# Radial-V_Alim.net
KiCad netlist of a schematic drawn in EAGLE
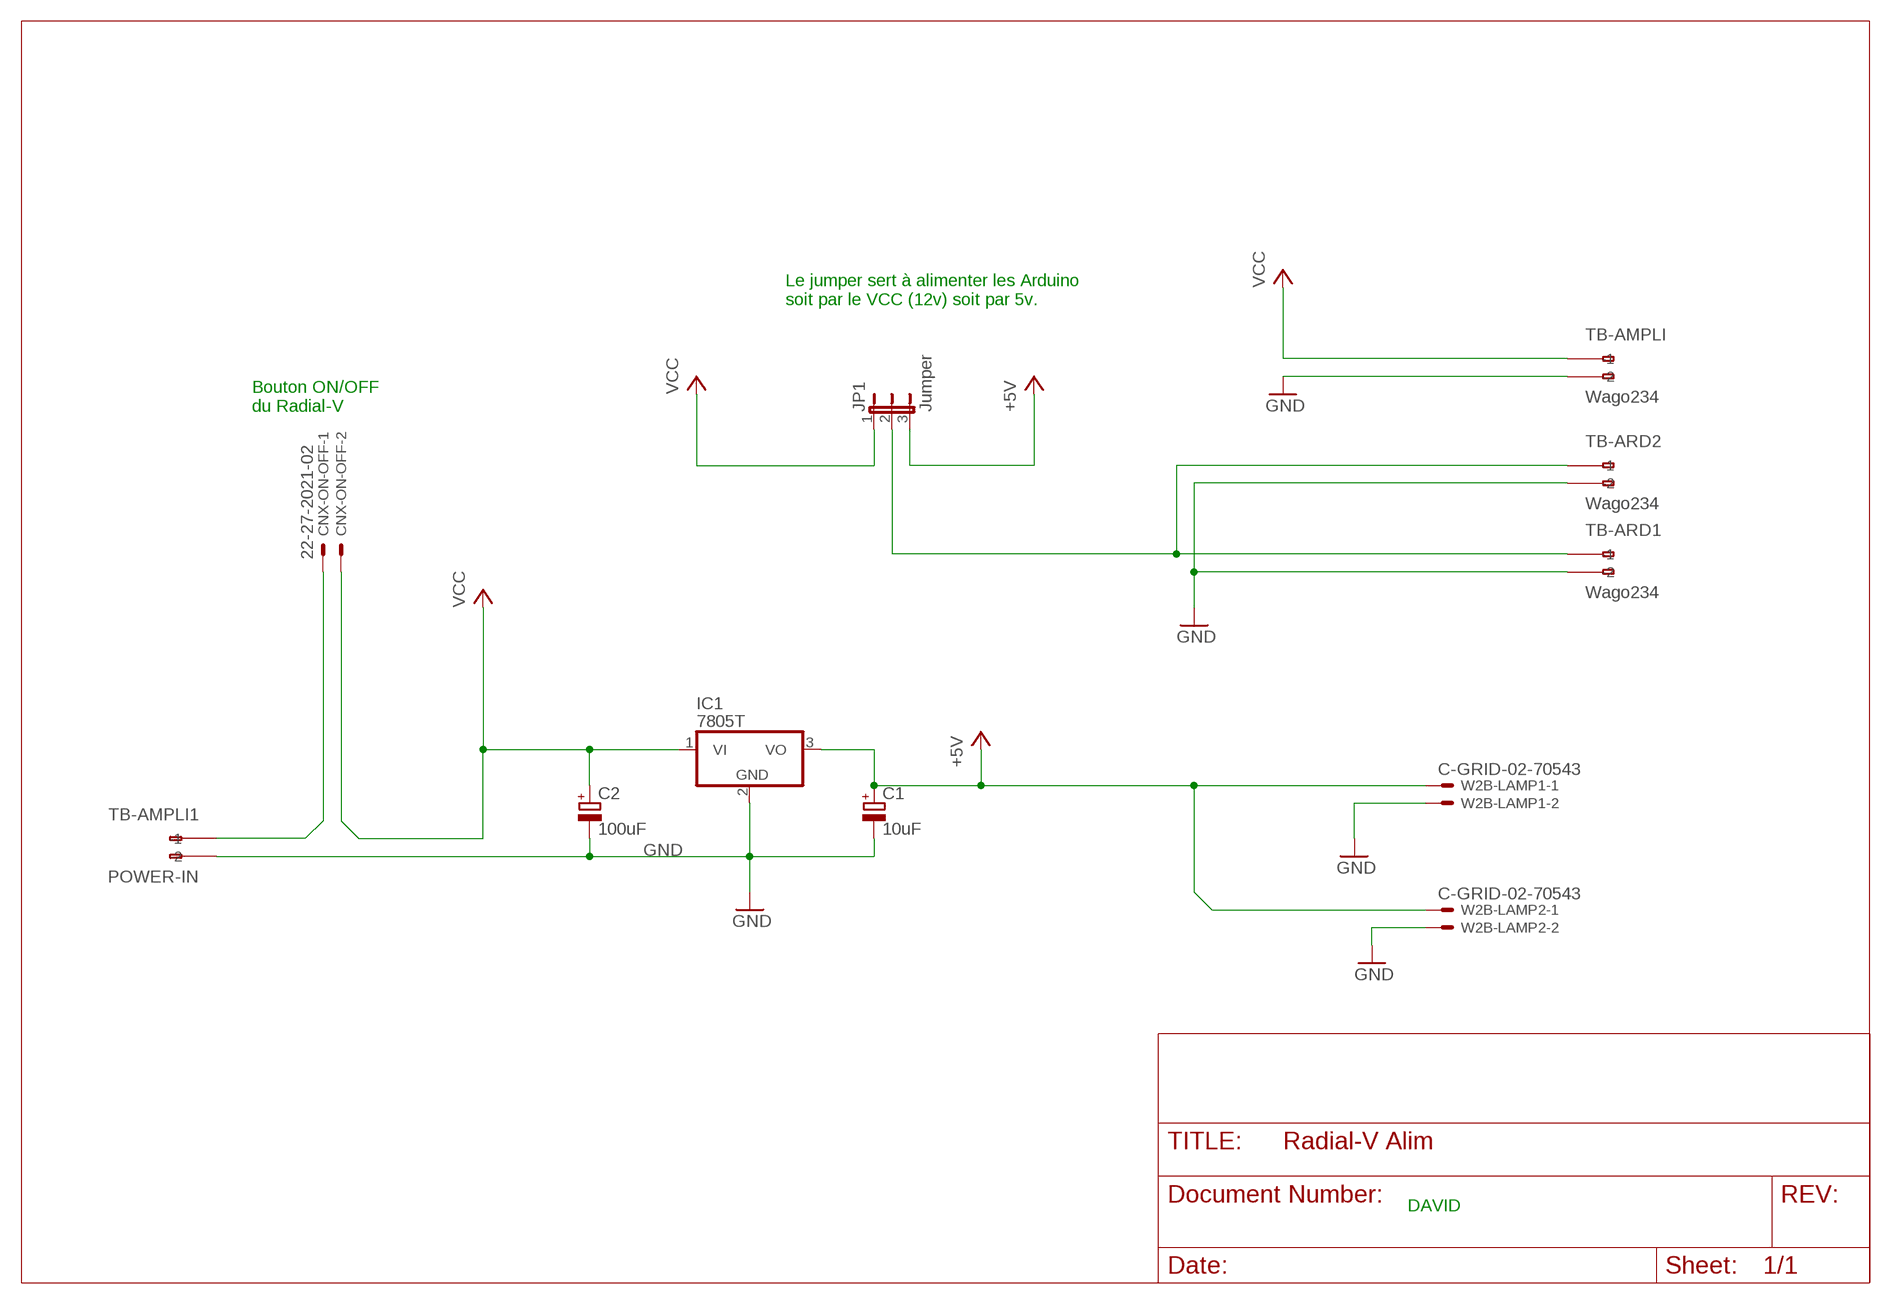
[diagram p0: schematic, sheet 1]

(export (version "E")
  (design (tool "Eeschema 10.0.6"))
  (components
    (comp (ref "C1")
      (value "10uF")
      (footprint "eagle-import:E5-5")
      (libsource (lib "eagle-import") (part "CPOL-EUE5-5"))
    )
    (comp (ref "C2")
      (value "100uF")
      (footprint "eagle-import:E22-10")
      (libsource (lib "eagle-import") (part "CPOL-EUE22-10AXIAL"))
    )
    (comp (ref "CNX-ON-OFF")
      (value "22-27-2021-02")
      (footprint "eagle-import:6410-02")
      (libsource (lib "eagle-import") (part "22-?-0227-2021"))
    )
    (comp (ref "IC1")
      (value "7805T")
      (footprint "eagle-import:TO220H")
      (libsource (lib "eagle-import") (part "78T05"))
    )
    (comp (ref "JP1")
      (value "Jumper")
      (footprint "eagle-import:JP2")
      (libsource (lib "eagle-import") (part "JP2E"))
    )
    (comp (ref "TB-AMPLI")
      (value "Wago234")
      (footprint "eagle-import:234-202")
      (fields (field (name "MPN") "234-202"))
      (libsource (lib "eagle-import") (part "234-202"))
    )
    (comp (ref "TB-AMPLI1")
      (value "POWER-IN")
      (footprint "eagle-import:234-202")
      (fields (field (name "MPN") "234-202"))
      (libsource (lib "eagle-import") (part "234-202"))
    )
    (comp (ref "TB-ARD1")
      (value "Wago234")
      (footprint "eagle-import:234-202")
      (fields (field (name "MPN") "234-202"))
      (libsource (lib "eagle-import") (part "234-202"))
    )
    (comp (ref "TB-ARD2")
      (value "Wago234")
      (footprint "eagle-import:234-202")
      (fields (field (name "MPN") "234-202"))
      (libsource (lib "eagle-import") (part "234-202"))
    )
    (comp (ref "W2B-LAMP1")
      (value "C-GRID-02-70543")
      (footprint "eagle-import:70543-02")
      (libsource (lib "eagle-import") (part "C-GRID-02-70543"))
    )
    (comp (ref "W2B-LAMP2")
      (value "C-GRID-02-70543")
      (footprint "eagle-import:70543-02")
      (libsource (lib "eagle-import") (part "C-GRID-02-70543"))
    )
  )
  (nets
    (net (code "1") (name "+5V") (class "Default")
      (node (ref "C1") (pin "+") (pinfunction "+_+") (pintype "passive"))
      (node (ref "IC1") (pin "3") (pinfunction "VO_3") (pintype "passive"))
      (node (ref "JP1") (pin "3") (pinfunction "3_3") (pintype "passive"))
      (node (ref "W2B-LAMP1") (pin "1") (pinfunction "S_1") (pintype "passive"))
      (node (ref "W2B-LAMP2") (pin "1") (pinfunction "S_1") (pintype "passive"))
    )
    (net (code "2") (name "GND") (class "Default")
      (node (ref "C1") (pin "-") (pinfunction "-_-") (pintype "passive"))
      (node (ref "C2") (pin "-") (pinfunction "-_-") (pintype "passive"))
      (node (ref "IC1") (pin "2") (pinfunction "GND_2") (pintype "passive"))
      (node (ref "TB-AMPLI") (pin "A2") (pinfunction "-2_A2") (pintype "passive"))
      (node (ref "TB-AMPLI1") (pin "A2") (pinfunction "-2_A2") (pintype "passive"))
      (node (ref "TB-ARD1") (pin "A2") (pinfunction "-2_A2") (pintype "passive"))
      (node (ref "TB-ARD2") (pin "A2") (pinfunction "-2_A2") (pintype "passive"))
      (node (ref "W2B-LAMP1") (pin "2") (pinfunction "S_2") (pintype "passive"))
      (node (ref "W2B-LAMP2") (pin "2") (pinfunction "S_2") (pintype "passive"))
    )
    (net (code "3") (name "Net-(CNX-ON-OFFA-S)") (class "Default")
      (node (ref "CNX-ON-OFF") (pin "1") (pinfunction "S_1") (pintype "passive"))
      (node (ref "TB-AMPLI1") (pin "A1") (pinfunction "-1_A1") (pintype "passive"))
    )
    (net (code "4") (name "Net-(TB-ARD1--1)") (class "Default")
      (node (ref "JP1") (pin "2") (pinfunction "2_2") (pintype "passive"))
      (node (ref "TB-ARD1") (pin "A1") (pinfunction "-1_A1") (pintype "passive"))
      (node (ref "TB-ARD2") (pin "A1") (pinfunction "-1_A1") (pintype "passive"))
    )
    (net (code "5") (name "VCC") (class "Default")
      (node (ref "C2") (pin "+") (pinfunction "+_+") (pintype "passive"))
      (node (ref "CNX-ON-OFF") (pin "2") (pinfunction "S_2") (pintype "passive"))
      (node (ref "IC1") (pin "1") (pinfunction "VI_1") (pintype "input"))
      (node (ref "JP1") (pin "1") (pinfunction "1_1") (pintype "passive"))
      (node (ref "TB-AMPLI") (pin "A1") (pinfunction "-1_A1") (pintype "passive"))
    )
    (net (code "6") (name "unconnected-(TB-AMPLI-B-1-PadB1)") (class "Default")
      (node (ref "TB-AMPLI") (pin "B1") (pinfunction "B-1_B1") (pintype "passive"))
    )
    (net (code "7") (name "unconnected-(TB-AMPLI-B-2-PadB2)") (class "Default")
      (node (ref "TB-AMPLI") (pin "B2") (pinfunction "B-2_B2") (pintype "passive"))
    )
    (net (code "8") (name "unconnected-(TB-AMPLI1-B-1-PadB1)") (class "Default")
      (node (ref "TB-AMPLI1") (pin "B1") (pinfunction "B-1_B1") (pintype "passive"))
    )
    (net (code "9") (name "unconnected-(TB-AMPLI1-B-2-PadB2)") (class "Default")
      (node (ref "TB-AMPLI1") (pin "B2") (pinfunction "B-2_B2") (pintype "passive"))
    )
    (net (code "10") (name "unconnected-(TB-ARD1-B-1-PadB1)") (class "Default")
      (node (ref "TB-ARD1") (pin "B1") (pinfunction "B-1_B1") (pintype "passive"))
    )
    (net (code "11") (name "unconnected-(TB-ARD1-B-2-PadB2)") (class "Default")
      (node (ref "TB-ARD1") (pin "B2") (pinfunction "B-2_B2") (pintype "passive"))
    )
    (net (code "12") (name "unconnected-(TB-ARD2-B-1-PadB1)") (class "Default")
      (node (ref "TB-ARD2") (pin "B1") (pinfunction "B-1_B1") (pintype "passive"))
    )
    (net (code "13") (name "unconnected-(TB-ARD2-B-2-PadB2)") (class "Default")
      (node (ref "TB-ARD2") (pin "B2") (pinfunction "B-2_B2") (pintype "passive"))
    )
  )
)
